# pots_mcu.net
KiCad netlist of a schematic drawn in EAGLE
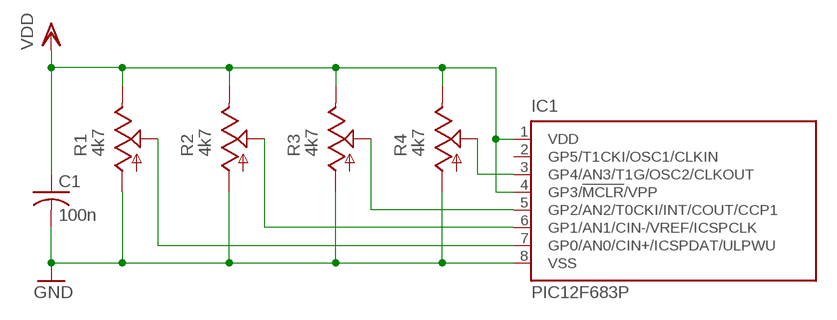
[diagram p0: schematic, sheet 1]

(export (version "E")
  (design (tool "Eeschema 10.0.6"))
  (components
    (comp (ref "C1")
      (value "100n")
      (footprint "eagle-import:C025-025X050")
      (libsource (lib "eagle-import") (part "C-US025-025X050"))
    )
    (comp (ref "IC1")
      (value "PIC12F683P")
      (footprint "eagle-import:DIL8")
      (fields (field (name "MF") "MICROCHIP") (field (name "MPN") "PIC12F683-I/P"))
      (libsource (lib "eagle-import") (part "PIC12F683P"))
    )
    (comp (ref "R1")
      (value "4k7")
      (footprint "eagle-import:EVUE")
      (libsource (lib "eagle-import") (part "US-EVUE2A"))
    )
    (comp (ref "R2")
      (value "4k7")
      (footprint "eagle-import:EVUE")
      (libsource (lib "eagle-import") (part "US-EVUE2A"))
    )
    (comp (ref "R3")
      (value "4k7")
      (footprint "eagle-import:EVUE")
      (libsource (lib "eagle-import") (part "US-EVUE2A"))
    )
    (comp (ref "R4")
      (value "4k7")
      (footprint "eagle-import:EVUE")
      (libsource (lib "eagle-import") (part "US-EVUE2A"))
    )
  )
  (nets
    (net (code "1") (name "GND") (class "Default")
      (node (ref "C1") (pin "2") (pinfunction "2_2") (pintype "passive"))
      (node (ref "IC1") (pin "8") (pinfunction "VSS_8") (pintype "power_in"))
      (node (ref "R1") (pin "1") (pinfunction "A_1") (pintype "passive"))
      (node (ref "R2") (pin "1") (pinfunction "A_1") (pintype "passive"))
      (node (ref "R3") (pin "1") (pinfunction "A_1") (pintype "passive"))
      (node (ref "R4") (pin "1") (pinfunction "A_1") (pintype "passive"))
    )
    (net (code "2") (name "Net-(IC1-GP0{slash}AN0{slash}CIN+{slash}ICSPDAT{slash}ULPWU)") (class "Default")
      (node (ref "IC1") (pin "7") (pinfunction "GP0/AN0/CIN+/ICSPDAT/ULPWU_7") (pintype "bidirectional"))
      (node (ref "R1") (pin "2") (pinfunction "S_2") (pintype "passive"))
    )
    (net (code "3") (name "Net-(IC1-GP1{slash}AN1{slash}CIN-{slash}VREF{slash}ICSPCLK)") (class "Default")
      (node (ref "IC1") (pin "6") (pinfunction "GP1/AN1/CIN-/VREF/ICSPCLK_6") (pintype "bidirectional"))
      (node (ref "R2") (pin "2") (pinfunction "S_2") (pintype "passive"))
    )
    (net (code "4") (name "Net-(IC1-GP2{slash}AN2{slash}T0CKI{slash}INT{slash}COUT{slash}CCP1)") (class "Default")
      (node (ref "IC1") (pin "5") (pinfunction "GP2/AN2/T0CKI/INT/COUT/CCP1_5") (pintype "bidirectional"))
      (node (ref "R3") (pin "2") (pinfunction "S_2") (pintype "passive"))
    )
    (net (code "5") (name "Net-(IC1-GP4{slash}AN3{slash}T1G{slash}OSC2{slash}CLKOUT)") (class "Default")
      (node (ref "IC1") (pin "3") (pinfunction "GP4/AN3/T1G/OSC2/CLKOUT_3") (pintype "bidirectional"))
      (node (ref "R4") (pin "2") (pinfunction "S_2") (pintype "passive"))
    )
    (net (code "6") (name "VDD") (class "Default")
      (node (ref "C1") (pin "1") (pinfunction "1_1") (pintype "passive"))
      (node (ref "IC1") (pin "1") (pinfunction "VDD_1") (pintype "power_in"))
      (node (ref "IC1") (pin "4") (pinfunction "GP3/~{MCLR}/VPP_4") (pintype "bidirectional"))
      (node (ref "R1") (pin "3") (pinfunction "E_3") (pintype "passive"))
      (node (ref "R2") (pin "3") (pinfunction "E_3") (pintype "passive"))
      (node (ref "R3") (pin "3") (pinfunction "E_3") (pintype "passive"))
      (node (ref "R4") (pin "3") (pinfunction "E_3") (pintype "passive"))
    )
    (net (code "7") (name "unconnected-(IC1-GP5{slash}T1CKI{slash}OSC1{slash}CLKIN-Pad2)") (class "Default")
      (node (ref "IC1") (pin "2") (pinfunction "GP5/T1CKI/OSC1/CLKIN_2") (pintype "bidirectional"))
    )
  )
)
